# Motor_Driver.net
KiCad netlist of a schematic drawn in EAGLE
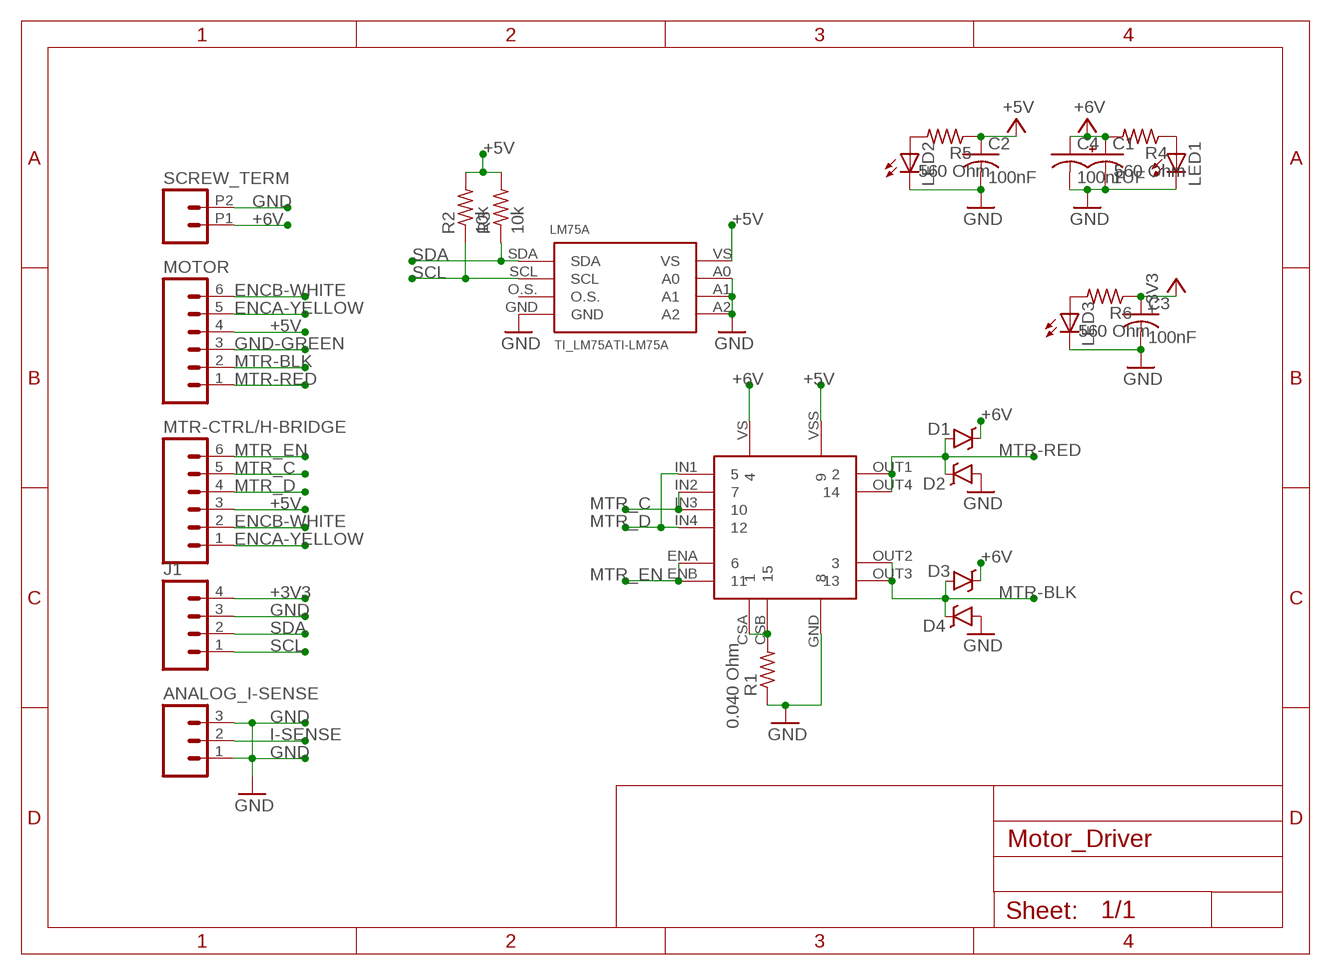
[diagram p0: schematic, sheet 1]

(export (version "E")
  (design (tool "Eeschema 10.0.6"))
  (components
    (comp (ref "ANALOG_I-SENSE")
      (value "M03PTH")
      (footprint "eagle-import:1X03")
      (libsource (lib "eagle-import") (part "M03PTH"))
    )
    (comp (ref "C1")
      (value "1UF")
      (footprint "eagle-import:CPOL-RADIAL-1UF-50V-KIT")
      (libsource (lib "eagle-import") (part "1UF-50V-20%(PTH)KIT"))
    )
    (comp (ref "C2")
      (value "100nF")
      (footprint "eagle-import:C1206")
      (libsource (lib "eagle-import") (part "C-USC1206"))
    )
    (comp (ref "C3")
      (value "100nF")
      (footprint "eagle-import:C1206")
      (libsource (lib "eagle-import") (part "C-USC1206"))
    )
    (comp (ref "C4")
      (value "100nF")
      (footprint "eagle-import:C1206")
      (libsource (lib "eagle-import") (part "C-USC1206"))
    )
    (comp (ref "D1")
      (value "B340A")
      (footprint "eagle-import:SMA-DIODE")
      (libsource (lib "eagle-import") (part "DIODE-SCHOTTKY-B340A"))
    )
    (comp (ref "D2")
      (value "B340A")
      (footprint "eagle-import:SMA-DIODE")
      (libsource (lib "eagle-import") (part "DIODE-SCHOTTKY-B340A"))
    )
    (comp (ref "D3")
      (value "B340A")
      (footprint "eagle-import:SMA-DIODE")
      (libsource (lib "eagle-import") (part "DIODE-SCHOTTKY-B340A"))
    )
    (comp (ref "D4")
      (value "B340A")
      (footprint "eagle-import:SMA-DIODE")
      (libsource (lib "eagle-import") (part "DIODE-SCHOTTKY-B340A"))
    )
    (comp (ref "J1")
      (value "M04PTH")
      (footprint "eagle-import:1X04")
      (libsource (lib "eagle-import") (part "M04PTH"))
    )
    (comp (ref "LED1")
      (value "LEDSMT1206")
      (footprint "eagle-import:1206")
      (libsource (lib "eagle-import") (part "LEDSMT1206"))
    )
    (comp (ref "LED2")
      (value "LEDSMT1206")
      (footprint "eagle-import:1206")
      (libsource (lib "eagle-import") (part "LEDSMT1206"))
    )
    (comp (ref "LED3")
      (value "LEDSMT1206")
      (footprint "eagle-import:1206")
      (libsource (lib "eagle-import") (part "LEDSMT1206"))
    )
    (comp (ref "LM75A")
      (value "TI_LM75ATI-LM75A")
      (footprint "eagle-import:TI_LM75A")
      (libsource (lib "eagle-import") (part "TI_LM75ATI-LM75A"))
    )
    (comp (ref "MOTOR")
      (value "M06SILK_FEMALE_PTH")
      (footprint "eagle-import:1X06")
      (libsource (lib "eagle-import") (part "M06SILK_FEMALE_PTH"))
    )
    (comp (ref "MTR-CTRL/H-BRIDGE")
      (value "M06SILK_FEMALE_PTH")
      (footprint "eagle-import:1X06")
      (libsource (lib "eagle-import") (part "M06SILK_FEMALE_PTH"))
    )
    (comp (ref "R1")
      (value "0.040 Ohm")
      (footprint "eagle-import:M0805")
      (libsource (lib "eagle-import") (part "R-US_M0805"))
    )
    (comp (ref "R2")
      (value "10k")
      (footprint "eagle-import:M1206")
      (libsource (lib "eagle-import") (part "R-US_M1206"))
    )
    (comp (ref "R3")
      (value "10k")
      (footprint "eagle-import:M1206")
      (libsource (lib "eagle-import") (part "R-US_M1206"))
    )
    (comp (ref "R4")
      (value "560 Ohm")
      (footprint "eagle-import:M0805")
      (libsource (lib "eagle-import") (part "R-US_M0805"))
    )
    (comp (ref "R5")
      (value "560 Ohm")
      (footprint "eagle-import:M0805")
      (libsource (lib "eagle-import") (part "R-US_M0805"))
    )
    (comp (ref "R6")
      (value "560 Ohm")
      (footprint "eagle-import:M0805")
      (libsource (lib "eagle-import") (part "R-US_M0805"))
    )
    (comp (ref "SCREW_TERM")
      (value "M022.54MM_SCREWTERM")
      (footprint "eagle-import:1X02_2.54_SCREWTERM")
      (libsource (lib "eagle-import") (part "M022.54MM_SCREWTERM"))
    )
    (comp (ref "U$1")
      (value "STL298N")
      (footprint "eagle-import:STL298N")
      (libsource (lib "eagle-import") (part "STL298N"))
    )
  )
  (nets
    (net (code "1") (name "+3V3") (class "Default")
      (node (ref "C3") (pin "1") (pinfunction "1_1") (pintype "passive"))
      (node (ref "J1") (pin "4") (pinfunction "4_4") (pintype "passive"))
      (node (ref "R6") (pin "1") (pinfunction "1_1") (pintype "passive"))
    )
    (net (code "2") (name "+5V") (class "Default")
      (node (ref "C2") (pin "1") (pinfunction "1_1") (pintype "passive"))
      (node (ref "LM75A") (pin "VS") (pinfunction "VS_VS") (pintype "bidirectional"))
      (node (ref "MOTOR") (pin "4") (pinfunction "4_4") (pintype "passive"))
      (node (ref "MTR-CTRL/H-BRIDGE") (pin "3") (pinfunction "3_3") (pintype "passive"))
      (node (ref "R2") (pin "2") (pinfunction "2_2") (pintype "passive"))
      (node (ref "R3") (pin "2") (pinfunction "2_2") (pintype "passive"))
      (node (ref "R5") (pin "1") (pinfunction "1_1") (pintype "passive"))
      (node (ref "U$1") (pin "VSS") (pinfunction "9_VSS") (pintype "bidirectional"))
    )
    (net (code "3") (name "+6V") (class "Default")
      (node (ref "C1") (pin "1") (pinfunction "+_1") (pintype "passive"))
      (node (ref "C4") (pin "1") (pinfunction "1_1") (pintype "passive"))
      (node (ref "D1") (pin "C") (pinfunction "C_C") (pintype "passive"))
      (node (ref "D3") (pin "C") (pinfunction "C_C") (pintype "passive"))
      (node (ref "R4") (pin "2") (pinfunction "2_2") (pintype "passive"))
      (node (ref "SCREW_TERM") (pin "P1") (pinfunction "1_P1") (pintype "passive"))
      (node (ref "U$1") (pin "VS") (pinfunction "4_VS") (pintype "bidirectional"))
    )
    (net (code "4") (name "/ENCA-YELLOW") (class "Default")
      (node (ref "MOTOR") (pin "5") (pinfunction "5_5") (pintype "passive"))
      (node (ref "MTR-CTRL/H-BRIDGE") (pin "1") (pinfunction "1_1") (pintype "passive"))
    )
    (net (code "5") (name "/ENCB-WHITE") (class "Default")
      (node (ref "MOTOR") (pin "6") (pinfunction "6_6") (pintype "passive"))
      (node (ref "MTR-CTRL/H-BRIDGE") (pin "2") (pinfunction "2_2") (pintype "passive"))
    )
    (net (code "6") (name "/GND-GREEN") (class "Default")
      (node (ref "MOTOR") (pin "3") (pinfunction "3_3") (pintype "passive"))
    )
    (net (code "7") (name "/I-SENSE") (class "Default")
      (node (ref "ANALOG_I-SENSE") (pin "2") (pinfunction "2_2") (pintype "passive"))
    )
    (net (code "8") (name "/MTR-BLK") (class "Default")
      (node (ref "D3") (pin "A") (pinfunction "A_A") (pintype "passive"))
      (node (ref "D4") (pin "C") (pinfunction "C_C") (pintype "passive"))
      (node (ref "MOTOR") (pin "2") (pinfunction "2_2") (pintype "passive"))
      (node (ref "U$1") (pin "OUT2") (pinfunction "3_OUT2") (pintype "bidirectional"))
      (node (ref "U$1") (pin "OUT3") (pinfunction "13_OUT3") (pintype "bidirectional"))
    )
    (net (code "9") (name "/MTR-RED") (class "Default")
      (node (ref "D1") (pin "A") (pinfunction "A_A") (pintype "passive"))
      (node (ref "D2") (pin "C") (pinfunction "C_C") (pintype "passive"))
      (node (ref "MOTOR") (pin "1") (pinfunction "1_1") (pintype "passive"))
      (node (ref "U$1") (pin "OUT1") (pinfunction "2_OUT1") (pintype "bidirectional"))
      (node (ref "U$1") (pin "OUT4") (pinfunction "14_OUT4") (pintype "bidirectional"))
    )
    (net (code "10") (name "/MTR_C") (class "Default")
      (node (ref "MTR-CTRL/H-BRIDGE") (pin "5") (pinfunction "5_5") (pintype "passive"))
      (node (ref "U$1") (pin "IN2") (pinfunction "7_IN2") (pintype "bidirectional"))
      (node (ref "U$1") (pin "IN3") (pinfunction "10_IN3") (pintype "bidirectional"))
    )
    (net (code "11") (name "/MTR_D") (class "Default")
      (node (ref "MTR-CTRL/H-BRIDGE") (pin "4") (pinfunction "4_4") (pintype "passive"))
      (node (ref "U$1") (pin "IN1") (pinfunction "5_IN1") (pintype "bidirectional"))
      (node (ref "U$1") (pin "IN4") (pinfunction "12_IN4") (pintype "bidirectional"))
    )
    (net (code "12") (name "/MTR_EN") (class "Default")
      (node (ref "MTR-CTRL/H-BRIDGE") (pin "6") (pinfunction "6_6") (pintype "passive"))
      (node (ref "U$1") (pin "ENA") (pinfunction "6_ENA") (pintype "bidirectional"))
      (node (ref "U$1") (pin "ENB") (pinfunction "11_ENB") (pintype "bidirectional"))
    )
    (net (code "13") (name "/SCL") (class "Default")
      (node (ref "J1") (pin "1") (pinfunction "1_1") (pintype "passive"))
      (node (ref "LM75A") (pin "SCL") (pinfunction "SCL_SCL") (pintype "bidirectional"))
      (node (ref "R2") (pin "1") (pinfunction "1_1") (pintype "passive"))
    )
    (net (code "14") (name "/SDA") (class "Default")
      (node (ref "J1") (pin "2") (pinfunction "2_2") (pintype "passive"))
      (node (ref "LM75A") (pin "SDA") (pinfunction "SDA_SDA") (pintype "bidirectional"))
      (node (ref "R3") (pin "1") (pinfunction "1_1") (pintype "passive"))
    )
    (net (code "15") (name "GND") (class "Default")
      (node (ref "ANALOG_I-SENSE") (pin "1") (pinfunction "1_1") (pintype "passive"))
      (node (ref "ANALOG_I-SENSE") (pin "3") (pinfunction "3_3") (pintype "passive"))
      (node (ref "C1") (pin "2") (pinfunction "-_2") (pintype "passive"))
      (node (ref "C2") (pin "2") (pinfunction "2_2") (pintype "passive"))
      (node (ref "C3") (pin "2") (pinfunction "2_2") (pintype "passive"))
      (node (ref "C4") (pin "2") (pinfunction "2_2") (pintype "passive"))
      (node (ref "D2") (pin "A") (pinfunction "A_A") (pintype "passive"))
      (node (ref "D4") (pin "A") (pinfunction "A_A") (pintype "passive"))
      (node (ref "J1") (pin "3") (pinfunction "3_3") (pintype "passive"))
      (node (ref "LED1") (pin "C") (pinfunction "C_C") (pintype "passive"))
      (node (ref "LED2") (pin "C") (pinfunction "C_C") (pintype "passive"))
      (node (ref "LED3") (pin "C") (pinfunction "C_C") (pintype "passive"))
      (node (ref "LM75A") (pin "A0") (pinfunction "A0_A0") (pintype "bidirectional"))
      (node (ref "LM75A") (pin "A1") (pinfunction "A1_A1") (pintype "bidirectional"))
      (node (ref "LM75A") (pin "A2") (pinfunction "A2_A2") (pintype "bidirectional"))
      (node (ref "LM75A") (pin "GND") (pinfunction "GND_GND") (pintype "bidirectional"))
      (node (ref "R1") (pin "1") (pinfunction "1_1") (pintype "passive"))
      (node (ref "SCREW_TERM") (pin "P2") (pinfunction "2_P2") (pintype "passive"))
      (node (ref "U$1") (pin "GND") (pinfunction "8_GND") (pintype "bidirectional"))
    )
    (net (code "16") (name "Net-(LED1-PadA)") (class "Default")
      (node (ref "LED1") (pin "A") (pinfunction "A_A") (pintype "passive"))
      (node (ref "R4") (pin "1") (pinfunction "1_1") (pintype "passive"))
    )
    (net (code "17") (name "Net-(LED2-PadA)") (class "Default")
      (node (ref "LED2") (pin "A") (pinfunction "A_A") (pintype "passive"))
      (node (ref "R5") (pin "2") (pinfunction "2_2") (pintype "passive"))
    )
    (net (code "18") (name "Net-(LED3-PadA)") (class "Default")
      (node (ref "LED3") (pin "A") (pinfunction "A_A") (pintype "passive"))
      (node (ref "R6") (pin "2") (pinfunction "2_2") (pintype "passive"))
    )
    (net (code "19") (name "Net-(U$1-1)") (class "Default")
      (node (ref "R1") (pin "2") (pinfunction "2_2") (pintype "passive"))
      (node (ref "U$1") (pin "CSA") (pinfunction "1_CSA") (pintype "bidirectional"))
      (node (ref "U$1") (pin "CSB") (pinfunction "15_CSB") (pintype "bidirectional"))
    )
    (net (code "20") (name "unconnected-(LM75A-PadO.S.)") (class "Default")
      (node (ref "LM75A") (pin "O.S.") (pinfunction "O.S._O.S.") (pintype "bidirectional"))
    )
  )
)
